# DC_LINK.net
KiCad netlist of a schematic drawn in Altium Designer
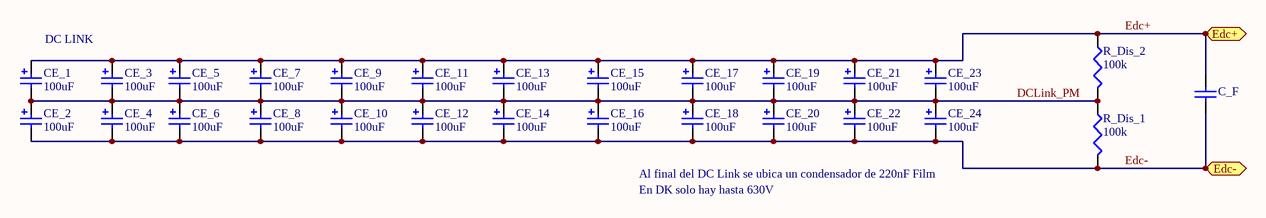
[diagram p0: DC_LINK.SchDoc]

(export (version "E")
  (design (tool "Eeschema 10.0.6"))
  (components
    (comp (ref "CE_1")
      (value "100uF")
      (footprint "COND_ELECTRO")
      (libsource (lib "aislados") (part "Condensador DC-Link"))
    )
    (comp (ref "CE_2")
      (value "100uF")
      (footprint "COND_ELECTRO")
      (libsource (lib "aislados") (part "Condensador DC-Link"))
    )
    (comp (ref "CE_3")
      (value "100uF")
      (footprint "COND_ELECTRO")
      (libsource (lib "aislados") (part "Condensador DC-Link"))
    )
    (comp (ref "CE_4")
      (value "100uF")
      (footprint "COND_ELECTRO")
      (libsource (lib "aislados") (part "Condensador DC-Link"))
    )
    (comp (ref "CE_5")
      (value "100uF")
      (footprint "COND_ELECTRO")
      (libsource (lib "aislados") (part "Condensador DC-Link"))
    )
    (comp (ref "CE_6")
      (value "100uF")
      (footprint "COND_ELECTRO")
      (libsource (lib "aislados") (part "Condensador DC-Link"))
    )
    (comp (ref "CE_7")
      (value "100uF")
      (footprint "COND_ELECTRO")
      (libsource (lib "aislados") (part "Condensador DC-Link"))
    )
    (comp (ref "CE_8")
      (value "100uF")
      (footprint "COND_ELECTRO")
      (libsource (lib "aislados") (part "Condensador DC-Link"))
    )
    (comp (ref "CE_9")
      (value "100uF")
      (footprint "COND_ELECTRO")
      (libsource (lib "aislados") (part "Condensador DC-Link"))
    )
    (comp (ref "CE_10")
      (value "100uF")
      (footprint "COND_ELECTRO")
      (libsource (lib "aislados") (part "Condensador DC-Link"))
    )
    (comp (ref "CE_11")
      (value "100uF")
      (footprint "COND_ELECTRO")
      (libsource (lib "aislados") (part "Condensador DC-Link"))
    )
    (comp (ref "CE_12")
      (value "100uF")
      (footprint "COND_ELECTRO")
      (libsource (lib "aislados") (part "Condensador DC-Link"))
    )
    (comp (ref "CE_13")
      (value "100uF")
      (footprint "COND_ELECTRO")
      (libsource (lib "aislados") (part "Condensador DC-Link"))
    )
    (comp (ref "CE_14")
      (value "100uF")
      (footprint "COND_ELECTRO")
      (libsource (lib "aislados") (part "Condensador DC-Link"))
    )
    (comp (ref "CE_15")
      (value "100uF")
      (footprint "COND_ELECTRO")
      (libsource (lib "aislados") (part "Condensador DC-Link"))
    )
    (comp (ref "CE_16")
      (value "100uF")
      (footprint "COND_ELECTRO")
      (libsource (lib "aislados") (part "Condensador DC-Link"))
    )
    (comp (ref "CE_17")
      (value "100uF")
      (footprint "COND_ELECTRO")
      (libsource (lib "aislados") (part "Condensador DC-Link"))
    )
    (comp (ref "CE_18")
      (value "100uF")
      (footprint "COND_ELECTRO")
      (libsource (lib "aislados") (part "Condensador DC-Link"))
    )
    (comp (ref "CE_19")
      (value "100uF")
      (footprint "COND_ELECTRO")
      (libsource (lib "aislados") (part "Condensador DC-Link"))
    )
    (comp (ref "CE_20")
      (value "100uF")
      (footprint "COND_ELECTRO")
      (libsource (lib "aislados") (part "Condensador DC-Link"))
    )
    (comp (ref "CE_21")
      (value "100uF")
      (footprint "COND_ELECTRO")
      (libsource (lib "aislados") (part "Condensador DC-Link"))
    )
    (comp (ref "CE_22")
      (value "100uF")
      (footprint "COND_ELECTRO")
      (libsource (lib "aislados") (part "Condensador DC-Link"))
    )
    (comp (ref "CE_23")
      (value "100uF")
      (footprint "COND_ELECTRO")
      (libsource (lib "aislados") (part "Condensador DC-Link"))
    )
    (comp (ref "CE_24")
      (value "100uF")
      (footprint "COND_ELECTRO")
      (libsource (lib "aislados") (part "Condensador DC-Link"))
    )
    (comp (ref "C_F")
      (value "Cap Semi")
      (footprint "CF_NN")
      (description "CAP FILM 0.22UF 10% 1KVDC RADIAL")
      (fields
        (field (name "DIGI-KEY PART NUMBER") "399-12820-ND")
        (field (name "MANUFACTURER PART NUMBER") "R71QR32204000K")
      )
      (libsource (lib "Miscellaneous Devices") (part "Cap Semi"))
    )
    (comp (ref "R_Dis_1")
      (value "100k")
      (footprint "TO-220")
      (description "RES 100K OHM 25W 1% TO220")
      (fields
        (field (name "DIGI-KEY PART NUMBER") "MP925-100KF-ND")
        (field (name "MANUFACTURER PART NUMBER") "MP925-100K-1%")
      )
      (libsource (lib "Miscellaneous Devices") (part "Res3"))
    )
    (comp (ref "R_Dis_2")
      (value "100k")
      (footprint "TO-220")
      (description "RES 100K OHM 25W 1% TO220")
      (fields
        (field (name "DIGI-KEY PART NUMBER") "MP925-100KF-ND")
        (field (name "MANUFACTURER PART NUMBER") "MP925-100K-1%")
      )
      (libsource (lib "Miscellaneous Devices") (part "Res3"))
    )
  )
  (nets
    (net (code "1") (name "/DCLink_PM") (class "Default")
      (node (ref "CE_1") (pin "2") (pinfunction "N_2") (pintype "passive"))
      (node (ref "CE_10") (pin "1") (pinfunction "P_1") (pintype "passive"))
      (node (ref "CE_11") (pin "2") (pinfunction "N_2") (pintype "passive"))
      (node (ref "CE_12") (pin "1") (pinfunction "P_1") (pintype "passive"))
      (node (ref "CE_13") (pin "2") (pinfunction "N_2") (pintype "passive"))
      (node (ref "CE_14") (pin "1") (pinfunction "P_1") (pintype "passive"))
      (node (ref "CE_15") (pin "2") (pinfunction "N_2") (pintype "passive"))
      (node (ref "CE_16") (pin "1") (pinfunction "P_1") (pintype "passive"))
      (node (ref "CE_17") (pin "2") (pinfunction "N_2") (pintype "passive"))
      (node (ref "CE_18") (pin "1") (pinfunction "P_1") (pintype "passive"))
      (node (ref "CE_19") (pin "2") (pinfunction "N_2") (pintype "passive"))
      (node (ref "CE_2") (pin "1") (pinfunction "P_1") (pintype "passive"))
      (node (ref "CE_20") (pin "1") (pinfunction "P_1") (pintype "passive"))
      (node (ref "CE_21") (pin "2") (pinfunction "N_2") (pintype "passive"))
      (node (ref "CE_22") (pin "1") (pinfunction "P_1") (pintype "passive"))
      (node (ref "CE_23") (pin "2") (pinfunction "N_2") (pintype "passive"))
      (node (ref "CE_24") (pin "1") (pinfunction "P_1") (pintype "passive"))
      (node (ref "CE_3") (pin "2") (pinfunction "N_2") (pintype "passive"))
      (node (ref "CE_4") (pin "1") (pinfunction "P_1") (pintype "passive"))
      (node (ref "CE_5") (pin "2") (pinfunction "N_2") (pintype "passive"))
      (node (ref "CE_6") (pin "1") (pinfunction "P_1") (pintype "passive"))
      (node (ref "CE_7") (pin "2") (pinfunction "N_2") (pintype "passive"))
      (node (ref "CE_8") (pin "1") (pinfunction "P_1") (pintype "passive"))
      (node (ref "CE_9") (pin "2") (pinfunction "N_2") (pintype "passive"))
      (node (ref "R_Dis_1") (pin "1") (pinfunction "1_1") (pintype "passive"))
      (node (ref "R_Dis_2") (pin "2") (pinfunction "2_2") (pintype "passive"))
    )
    (net (code "2") (name "/Edc+") (class "Default")
      (node (ref "CE_1") (pin "1") (pinfunction "P_1") (pintype "passive"))
      (node (ref "CE_11") (pin "1") (pinfunction "P_1") (pintype "passive"))
      (node (ref "CE_13") (pin "1") (pinfunction "P_1") (pintype "passive"))
      (node (ref "CE_15") (pin "1") (pinfunction "P_1") (pintype "passive"))
      (node (ref "CE_17") (pin "1") (pinfunction "P_1") (pintype "passive"))
      (node (ref "CE_19") (pin "1") (pinfunction "P_1") (pintype "passive"))
      (node (ref "CE_21") (pin "1") (pinfunction "P_1") (pintype "passive"))
      (node (ref "CE_23") (pin "1") (pinfunction "P_1") (pintype "passive"))
      (node (ref "CE_3") (pin "1") (pinfunction "P_1") (pintype "passive"))
      (node (ref "CE_5") (pin "1") (pinfunction "P_1") (pintype "passive"))
      (node (ref "CE_7") (pin "1") (pinfunction "P_1") (pintype "passive"))
      (node (ref "CE_9") (pin "1") (pinfunction "P_1") (pintype "passive"))
      (node (ref "C_F") (pin "2") (pinfunction "2_2") (pintype "passive"))
      (node (ref "R_Dis_2") (pin "1") (pinfunction "1_1") (pintype "passive"))
    )
    (net (code "3") (name "/Edc-") (class "Default")
      (node (ref "CE_10") (pin "2") (pinfunction "N_2") (pintype "passive"))
      (node (ref "CE_12") (pin "2") (pinfunction "N_2") (pintype "passive"))
      (node (ref "CE_14") (pin "2") (pinfunction "N_2") (pintype "passive"))
      (node (ref "CE_16") (pin "2") (pinfunction "N_2") (pintype "passive"))
      (node (ref "CE_18") (pin "2") (pinfunction "N_2") (pintype "passive"))
      (node (ref "CE_2") (pin "2") (pinfunction "N_2") (pintype "passive"))
      (node (ref "CE_20") (pin "2") (pinfunction "N_2") (pintype "passive"))
      (node (ref "CE_22") (pin "2") (pinfunction "N_2") (pintype "passive"))
      (node (ref "CE_24") (pin "2") (pinfunction "N_2") (pintype "passive"))
      (node (ref "CE_4") (pin "2") (pinfunction "N_2") (pintype "passive"))
      (node (ref "CE_6") (pin "2") (pinfunction "N_2") (pintype "passive"))
      (node (ref "CE_8") (pin "2") (pinfunction "N_2") (pintype "passive"))
      (node (ref "C_F") (pin "1") (pinfunction "1_1") (pintype "passive"))
      (node (ref "R_Dis_1") (pin "2") (pinfunction "2_2") (pintype "passive"))
    )
  )
)
